# Input_channel.net
KiCad netlist of a schematic drawn in Altium Designer
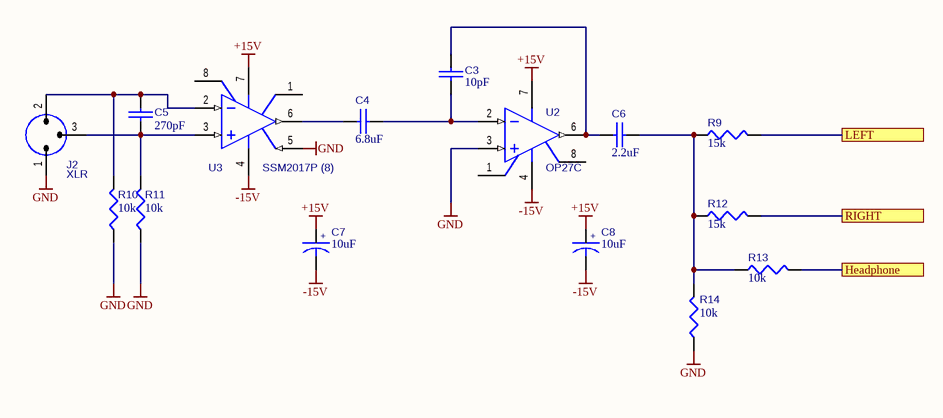
[diagram p0: Input channel.SchDoc]

(export (version "E")
  (design (tool "Eeschema 10.0.6"))
  (components
    (comp (ref "C3")
      (value "10pF")
      (footprint "RAD0.2")
      (description "Capacitor")
      (libsource (lib "*") (part "CAP"))
    )
    (comp (ref "C4")
      (value "6.8uF")
      (footprint "RB.2/.4-NP")
      (description "Capacitor")
      (libsource (lib "*") (part "CAP"))
    )
    (comp (ref "C5")
      (value "270pF")
      (footprint "RAD0.2")
      (description "Capacitor")
      (libsource (lib "*") (part "CAP"))
    )
    (comp (ref "C6")
      (value "2.2uF")
      (footprint "RB.2/.4-NP")
      (description "Capacitor")
      (libsource (lib "*") (part "CAP"))
    )
    (comp (ref "C7")
      (value "10uF")
      (footprint "RB.2/.4")
      (description "Bi-Polar Capacitor")
      (libsource (lib "*") (part "CAPACITOR POL"))
    )
    (comp (ref "C8")
      (value "10uF")
      (footprint "RB.2/.4")
      (description "Bi-Polar Capacitor")
      (libsource (lib "*") (part "CAPACITOR POL"))
    )
    (comp (ref "J2")
      (value "XLR")
      (footprint "XLR-FEMALE")
      (description "XLR connector, PCB mounted")
      (libsource (lib "*") (part "XLR"))
    )
    (comp (ref "R9")
      (value "15k")
      (footprint "AXIAL0.4")
      (description "Resistor")
      (libsource (lib "") (part "RES1_1"))
    )
    (comp (ref "R10")
      (value "10k")
      (footprint "AXIAL0.4")
      (description "Resistor")
      (libsource (lib "*") (part "RES1"))
    )
    (comp (ref "R11")
      (value "10k")
      (footprint "AXIAL0.4")
      (description "Resistor")
      (libsource (lib "*") (part "RES1"))
    )
    (comp (ref "R12")
      (value "15k")
      (footprint "AXIAL0.4")
      (description "Resistor")
      (libsource (lib "") (part "RES1_1"))
    )
    (comp (ref "R13")
      (value "10k")
      (footprint "AXIAL0.4")
      (description "Resistor")
      (libsource (lib "") (part "RES1_1"))
    )
    (comp (ref "R14")
      (value "10k")
      (footprint "AXIAL0.4")
      (description "Resistor")
      (libsource (lib "*") (part "RES1"))
    )
    (comp (ref "U2")
      (value "OP27C")
      (footprint "DIP8")
      (description "Low Noise, High Speed Precision Operational Amplifier")
      (libsource (lib "*") (part "OP27C"))
    )
    (comp (ref "U3")
      (value "SSM2017P (8)")
      (footprint "DIP8")
      (description "Self-Contained Audio Preamplifier")
      (libsource (lib "*") (part "SSM2017P (8)"))
    )
  )
  (nets
    (net (code "1") (name "+15V") (class "Default")
      (node (ref "C7") (pin "1") (pinfunction "1_1") (pintype "passive"))
      (node (ref "C8") (pin "1") (pinfunction "1_1") (pintype "passive"))
      (node (ref "U2") (pin "7") (pinfunction "V+_7") (pintype "power_in"))
      (node (ref "U3") (pin "7") (pinfunction "V+_7") (pintype "power_in"))
    )
    (net (code "2") (name "-15V") (class "Default")
      (node (ref "C7") (pin "2") (pinfunction "2_2") (pintype "passive"))
      (node (ref "C8") (pin "2") (pinfunction "2_2") (pintype "passive"))
      (node (ref "U2") (pin "4") (pinfunction "V-_4") (pintype "power_in"))
      (node (ref "U3") (pin "4") (pinfunction "V-_4") (pintype "power_in"))
    )
    (net (code "3") (name "/Headphone") (class "Default")
      (node (ref "R13") (pin "2") (pinfunction "2_2") (pintype "passive"))
    )
    (net (code "4") (name "/LEFT") (class "Default")
      (node (ref "R9") (pin "2") (pinfunction "2_2") (pintype "passive"))
    )
    (net (code "5") (name "/RIGHT") (class "Default")
      (node (ref "R12") (pin "2") (pinfunction "2_2") (pintype "passive"))
    )
    (net (code "6") (name "GND") (class "Default")
      (node (ref "J2") (pin "1") (pinfunction "1_1") (pintype "passive"))
      (node (ref "R10") (pin "1") (pinfunction "1_1") (pintype "passive"))
      (node (ref "R11") (pin "1") (pinfunction "1_1") (pintype "passive"))
      (node (ref "R14") (pin "1") (pinfunction "1_1") (pintype "passive"))
      (node (ref "U2") (pin "3") (pinfunction "+IN_3") (pintype "input"))
      (node (ref "U3") (pin "5") (pinfunction "REF_5") (pintype "input"))
    )
    (net (code "7") (name "Net-(C6-Pad2)") (class "Default")
      (node (ref "C6") (pin "2") (pinfunction "2_2") (pintype "passive"))
      (node (ref "R12") (pin "1") (pinfunction "1_1") (pintype "passive"))
      (node (ref "R13") (pin "1") (pinfunction "1_1") (pintype "passive"))
      (node (ref "R14") (pin "2") (pinfunction "2_2") (pintype "passive"))
      (node (ref "R9") (pin "1") (pinfunction "1_1") (pintype "passive"))
    )
    (net (code "8") (name "Net-(U2--IN)") (class "Default")
      (node (ref "C3") (pin "1") (pinfunction "1_1") (pintype "passive"))
      (node (ref "C4") (pin "2") (pinfunction "2_2") (pintype "passive"))
      (node (ref "U2") (pin "2") (pinfunction "-IN_2") (pintype "input"))
    )
    (net (code "9") (name "Net-(U2-OUT)") (class "Default")
      (node (ref "C3") (pin "2") (pinfunction "2_2") (pintype "passive"))
      (node (ref "C6") (pin "1") (pinfunction "1_1") (pintype "passive"))
      (node (ref "U2") (pin "6") (pinfunction "OUT_6") (pintype "output"))
    )
    (net (code "10") (name "Net-(U3-IN+)") (class "Default")
      (node (ref "C5") (pin "2") (pinfunction "2_2") (pintype "passive"))
      (node (ref "J2") (pin "3") (pinfunction "3_3") (pintype "passive"))
      (node (ref "R11") (pin "2") (pinfunction "2_2") (pintype "passive"))
      (node (ref "U3") (pin "3") (pinfunction "IN+_3") (pintype "input"))
    )
    (net (code "11") (name "Net-(U3-IN-)") (class "Default")
      (node (ref "C5") (pin "1") (pinfunction "1_1") (pintype "passive"))
      (node (ref "J2") (pin "2") (pinfunction "2_2") (pintype "passive"))
      (node (ref "R10") (pin "2") (pinfunction "2_2") (pintype "passive"))
      (node (ref "U3") (pin "2") (pinfunction "IN-_2") (pintype "input"))
    )
    (net (code "12") (name "Net-(U3-OUT)") (class "Default")
      (node (ref "C4") (pin "1") (pinfunction "1_1") (pintype "passive"))
      (node (ref "U3") (pin "6") (pinfunction "OUT_6") (pintype "output"))
    )
    (net (code "13") (name "unconnected-(U2-TRIM-Pad1)") (class "Default")
      (node (ref "U2") (pin "1") (pinfunction "TRIM_1") (pintype "passive"))
    )
    (net (code "14") (name "unconnected-(U2-TRIM-Pad8)") (class "Default")
      (node (ref "U2") (pin "8") (pinfunction "TRIM_8") (pintype "passive"))
    )
    (net (code "15") (name "unconnected-(U3-RG1-Pad1)") (class "Default")
      (node (ref "U3") (pin "1") (pinfunction "RG1_1") (pintype "passive"))
    )
    (net (code "16") (name "unconnected-(U3-RG2-Pad8)") (class "Default")
      (node (ref "U3") (pin "8") (pinfunction "RG2_8") (pintype "passive"))
    )
  )
)
